# Power_Supply_Section.net
KiCad netlist of a schematic drawn in Altium Designer
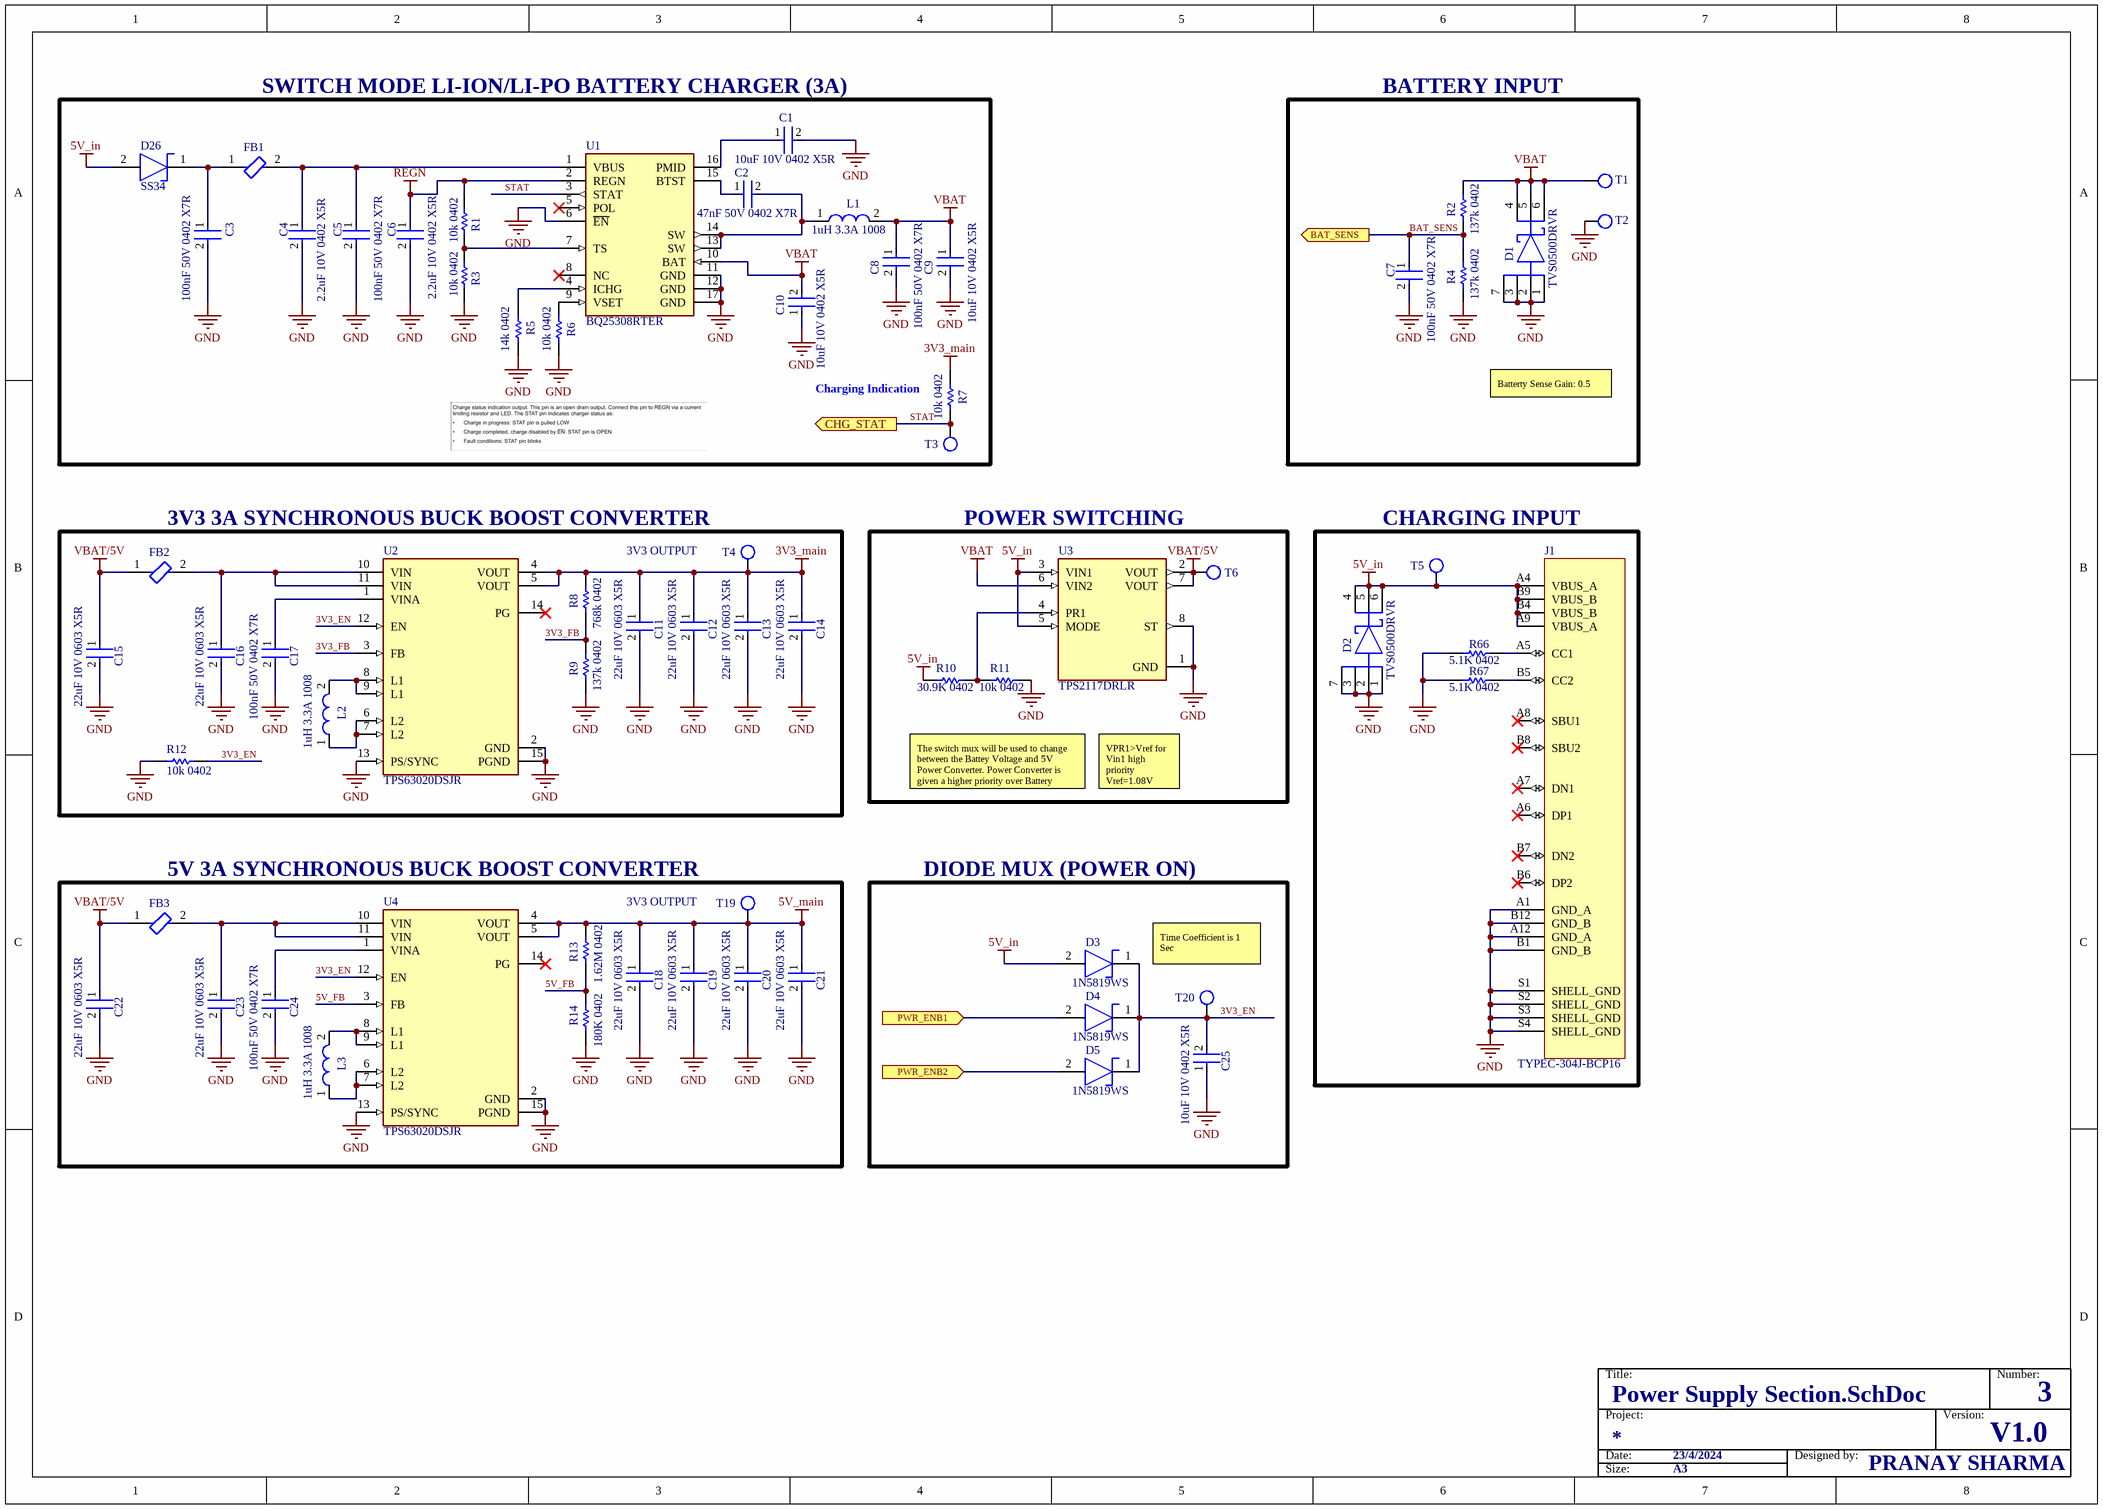
[diagram p0: Power Supply Section.SchDoc]

(export (version "E")
  (design (tool "Eeschema 10.0.6"))
  (components
    (comp (ref "C1")
      (value "10uF 10V 0402 X5R")
      (footprint "Res, Cap, Ind, LED, FB_Lib:0402 IPC CLASS C CAPACITOR")
      (libsource (lib "Capacitor_Lib") (part "10uF 10V 0402 X5R"))
    )
    (comp (ref "C2")
      (value "47nF 50V 0402 X7R")
      (footprint "Res, Cap, Ind, LED, FB_Lib:0402 IPC CLASS C CAPACITOR")
      (libsource (lib "Capacitor_Lib") (part "47nF 50V 0402 X7R"))
    )
    (comp (ref "C3")
      (value "100nF 50V 0402 X7R")
      (footprint "Res, Cap, Ind, LED, FB_Lib:0402 IPC CLASS C CAPACITOR")
      (libsource (lib "Capacitor_Lib") (part "100nF 50V 0402 X7R"))
    )
    (comp (ref "C4")
      (value "2.2uF 10V 0402 X5R")
      (footprint "Res, Cap, Ind, LED, FB_Lib:0402 IPC CLASS C CAPACITOR")
      (libsource (lib "Capacitor_Lib") (part "2.2uF 10V 0402 X5R"))
    )
    (comp (ref "C5")
      (value "100nF 50V 0402 X7R")
      (footprint "Res, Cap, Ind, LED, FB_Lib:0402 IPC CLASS C CAPACITOR")
      (libsource (lib "Capacitor_Lib") (part "100nF 50V 0402 X7R"))
    )
    (comp (ref "C6")
      (value "2.2uF 10V 0402 X5R")
      (footprint "Res, Cap, Ind, LED, FB_Lib:0402 IPC CLASS C CAPACITOR")
      (libsource (lib "Capacitor_Lib") (part "2.2uF 10V 0402 X5R"))
    )
    (comp (ref "C7")
      (value "100nF 50V 0402 X7R")
      (footprint "Res, Cap, Ind, LED, FB_Lib:0402 IPC CLASS C CAPACITOR")
      (libsource (lib "Capacitor_Lib") (part "100nF 50V 0402 X7R"))
    )
    (comp (ref "C8")
      (value "100nF 50V 0402 X7R")
      (footprint "Res, Cap, Ind, LED, FB_Lib:0402 IPC CLASS C CAPACITOR")
      (libsource (lib "Capacitor_Lib") (part "100nF 50V 0402 X7R"))
    )
    (comp (ref "C9")
      (value "10uF 10V 0402 X5R")
      (footprint "Res, Cap, Ind, LED, FB_Lib:0402 IPC CLASS C CAPACITOR")
      (libsource (lib "Capacitor_Lib") (part "10uF 10V 0402 X5R"))
    )
    (comp (ref "C10")
      (value "10uF 10V 0402 X5R")
      (footprint "Res, Cap, Ind, LED, FB_Lib:0402 IPC CLASS C CAPACITOR")
      (libsource (lib "Capacitor_Lib") (part "10uF 10V 0402 X5R"))
    )
    (comp (ref "C11")
      (value "22uF 10V 0603 X5R")
      (footprint "Res, Cap, Ind, LED, FB_Lib:0603 IPC CLASS C CAPACITOR")
      (libsource (lib "Capacitor_Lib") (part "22uF 10V 0603 X5R"))
    )
    (comp (ref "C12")
      (value "22uF 10V 0603 X5R")
      (footprint "Res, Cap, Ind, LED, FB_Lib:0603 IPC CLASS C CAPACITOR")
      (libsource (lib "Capacitor_Lib") (part "22uF 10V 0603 X5R"))
    )
    (comp (ref "C13")
      (value "22uF 10V 0603 X5R")
      (footprint "Res, Cap, Ind, LED, FB_Lib:0603 IPC CLASS C CAPACITOR")
      (libsource (lib "Capacitor_Lib") (part "22uF 10V 0603 X5R"))
    )
    (comp (ref "C14")
      (value "22uF 10V 0603 X5R")
      (footprint "Res, Cap, Ind, LED, FB_Lib:0603 IPC CLASS C CAPACITOR")
      (libsource (lib "Capacitor_Lib") (part "22uF 10V 0603 X5R"))
    )
    (comp (ref "C15")
      (value "22uF 10V 0603 X5R")
      (footprint "Res, Cap, Ind, LED, FB_Lib:0603 IPC CLASS C CAPACITOR")
      (libsource (lib "Capacitor_Lib") (part "22uF 10V 0603 X5R"))
    )
    (comp (ref "C16")
      (value "22uF 10V 0603 X5R")
      (footprint "Res, Cap, Ind, LED, FB_Lib:0603 IPC CLASS C CAPACITOR")
      (libsource (lib "Capacitor_Lib") (part "22uF 10V 0603 X5R"))
    )
    (comp (ref "C17")
      (value "100nF 50V 0402 X7R")
      (footprint "Res, Cap, Ind, LED, FB_Lib:0402 IPC CLASS C CAPACITOR")
      (libsource (lib "Capacitor_Lib") (part "100nF 50V 0402 X7R"))
    )
    (comp (ref "C18")
      (value "22uF 10V 0603 X5R")
      (footprint "Res, Cap, Ind, LED, FB_Lib:0603 IPC CLASS C CAPACITOR")
      (libsource (lib "Capacitor_Lib") (part "22uF 10V 0603 X5R"))
    )
    (comp (ref "C19")
      (value "22uF 10V 0603 X5R")
      (footprint "Res, Cap, Ind, LED, FB_Lib:0603 IPC CLASS C CAPACITOR")
      (libsource (lib "Capacitor_Lib") (part "22uF 10V 0603 X5R"))
    )
    (comp (ref "C20")
      (value "22uF 10V 0603 X5R")
      (footprint "Res, Cap, Ind, LED, FB_Lib:0603 IPC CLASS C CAPACITOR")
      (libsource (lib "Capacitor_Lib") (part "22uF 10V 0603 X5R"))
    )
    (comp (ref "C21")
      (value "22uF 10V 0603 X5R")
      (footprint "Res, Cap, Ind, LED, FB_Lib:0603 IPC CLASS C CAPACITOR")
      (libsource (lib "Capacitor_Lib") (part "22uF 10V 0603 X5R"))
    )
    (comp (ref "C22")
      (value "22uF 10V 0603 X5R")
      (footprint "Res, Cap, Ind, LED, FB_Lib:0603 IPC CLASS C CAPACITOR")
      (libsource (lib "Capacitor_Lib") (part "22uF 10V 0603 X5R"))
    )
    (comp (ref "C23")
      (value "22uF 10V 0603 X5R")
      (footprint "Res, Cap, Ind, LED, FB_Lib:0603 IPC CLASS C CAPACITOR")
      (libsource (lib "Capacitor_Lib") (part "22uF 10V 0603 X5R"))
    )
    (comp (ref "C24")
      (value "100nF 50V 0402 X7R")
      (footprint "Res, Cap, Ind, LED, FB_Lib:0402 IPC CLASS C CAPACITOR")
      (libsource (lib "Capacitor_Lib") (part "100nF 50V 0402 X7R"))
    )
    (comp (ref "C25")
      (value "10uF 10V 0402 X5R")
      (footprint "Res, Cap, Ind, LED, FB_Lib:0402 IPC CLASS C CAPACITOR")
      (libsource (lib "Capacitor_Lib") (part "10uF 10V 0402 X5R"))
    )
    (comp (ref "D1")
      (value "TVS0500DRVR")
      (footprint "Res, Cap, Ind, LED, FB_Lib:DRV0006A IPC-C")
      (libsource (lib "Diodes_Lib") (part "TVS0500DRVR"))
    )
    (comp (ref "D2")
      (value "TVS0500DRVR")
      (footprint "Res, Cap, Ind, LED, FB_Lib:DRV0006A IPC-C")
      (libsource (lib "Diodes_Lib") (part "TVS0500DRVR"))
    )
    (comp (ref "D3")
      (value "1N5819WS")
      (footprint "Res, Cap, Ind, LED, FB_Lib:SOD-323 IPC-C")
      (libsource (lib "Diodes_Lib") (part "1N5819WS"))
    )
    (comp (ref "D4")
      (value "1N5819WS")
      (footprint "Res, Cap, Ind, LED, FB_Lib:SOD-323 IPC-C")
      (libsource (lib "Diodes_Lib") (part "1N5819WS"))
    )
    (comp (ref "D5")
      (value "1N5819WS")
      (footprint "Res, Cap, Ind, LED, FB_Lib:SOD-323 IPC-C")
      (libsource (lib "Diodes_Lib") (part "1N5819WS"))
    )
    (comp (ref "D26")
      (value "SS34")
      (footprint "Res, Cap, Ind, LED, FB_Lib:SS3X Diode IPC-C")
      (libsource (lib "Diodes_Lib") (part "SS34"))
    )
    (comp (ref "FB1")
      (value "BLM21SP111SN1D")
      (footprint "Res, Cap, Ind, LED, FB_Lib:0603 IPC CLASS C FERRITE BEAD")
      (libsource (lib "Ferrite_Bead_Lib") (part "BLM21SP111SN1D"))
    )
    (comp (ref "FB2")
      (value "BLM21SP111SN1D")
      (footprint "Res, Cap, Ind, LED, FB_Lib:0603 IPC CLASS C FERRITE BEAD")
      (libsource (lib "Ferrite_Bead_Lib") (part "BLM21SP111SN1D"))
    )
    (comp (ref "FB3")
      (value "BLM21SP111SN1D")
      (footprint "Res, Cap, Ind, LED, FB_Lib:0603 IPC CLASS C FERRITE BEAD")
      (libsource (lib "Ferrite_Bead_Lib") (part "BLM21SP111SN1D"))
    )
    (comp (ref "J1")
      (value "TYPEC-304J-BCP16")
      (footprint "VALCON_CSP-USC16-TR")
      (libsource (lib "V1.0") (part "USB Type C"))
    )
    (comp (ref "L1")
      (value "1uH 3.3A 1008")
      (footprint "Res, Cap, Ind, LED, FB_Lib:1008 Inductor IPC-C")
      (libsource (lib "Inductor_Lib") (part "DFE252012F-1R0M=P2"))
    )
    (comp (ref "L2")
      (value "1uH 3.3A 1008")
      (footprint "Res, Cap, Ind, LED, FB_Lib:1008 Inductor IPC-C")
      (libsource (lib "Inductor_Lib") (part "DFE252012F-1R0M=P2"))
    )
    (comp (ref "L3")
      (value "1uH 3.3A 1008")
      (footprint "Res, Cap, Ind, LED, FB_Lib:1008 Inductor IPC-C")
      (libsource (lib "Inductor_Lib") (part "DFE252012F-1R0M=P2"))
    )
    (comp (ref "R1")
      (value "10k 0402")
      (footprint "Res, Cap, Ind, LED, FB_Lib:0402 IPC CLASS C RESISTOR")
      (libsource (lib "Resistor_Lib") (part "10k 1% 0402"))
    )
    (comp (ref "R2")
      (value "137k 0402")
      (footprint "Res, Cap, Ind, LED, FB_Lib:0402 IPC CLASS C RESISTOR")
      (libsource (lib "Resistor_Lib") (part "10k 1% 0402"))
    )
    (comp (ref "R3")
      (value "10k 0402")
      (footprint "Res, Cap, Ind, LED, FB_Lib:0402 IPC CLASS C RESISTOR")
      (libsource (lib "Resistor_Lib") (part "10k 1% 0402"))
    )
    (comp (ref "R4")
      (value "137k 0402")
      (footprint "Res, Cap, Ind, LED, FB_Lib:0402 IPC CLASS C RESISTOR")
      (libsource (lib "Resistor_Lib") (part "10k 1% 0402"))
    )
    (comp (ref "R5")
      (value "14k 0402")
      (footprint "Res, Cap, Ind, LED, FB_Lib:0402 IPC CLASS C RESISTOR")
      (libsource (lib "Resistor_Lib") (part "14k 1% 0402"))
    )
    (comp (ref "R6")
      (value "10k 0402")
      (footprint "Res, Cap, Ind, LED, FB_Lib:0402 IPC CLASS C RESISTOR")
      (libsource (lib "Resistor_Lib") (part "10k 1% 0402"))
    )
    (comp (ref "R7")
      (value "10k 0402")
      (footprint "Res, Cap, Ind, LED, FB_Lib:0402 IPC CLASS C RESISTOR")
      (libsource (lib "Resistor_Lib") (part "10k 1% 0402"))
    )
    (comp (ref "R8")
      (value "768k 0402")
      (footprint "Res, Cap, Ind, LED, FB_Lib:0402 IPC CLASS C RESISTOR")
      (libsource (lib "Resistor_Lib") (part "10k 1% 0402"))
    )
    (comp (ref "R9")
      (value "137k 0402")
      (footprint "Res, Cap, Ind, LED, FB_Lib:0402 IPC CLASS C RESISTOR")
      (libsource (lib "Resistor_Lib") (part "10k 1% 0402"))
    )
    (comp (ref "R10")
      (value "30.9K 0402")
      (footprint "Res, Cap, Ind, LED, FB_Lib:0402 IPC CLASS C RESISTOR")
      (libsource (lib "Resistor_Lib") (part "30.9K 1%  0402"))
    )
    (comp (ref "R11")
      (value "10k 0402")
      (footprint "Res, Cap, Ind, LED, FB_Lib:0402 IPC CLASS C RESISTOR")
      (libsource (lib "Resistor_Lib") (part "10k 1% 0402"))
    )
    (comp (ref "R12")
      (value "10k 0402")
      (footprint "Res, Cap, Ind, LED, FB_Lib:0402 IPC CLASS C RESISTOR")
      (libsource (lib "Resistor_Lib") (part "10k 1% 0402"))
    )
    (comp (ref "R13")
      (value "1.62M 0402")
      (footprint "Res, Cap, Ind, LED, FB_Lib:0402 IPC CLASS C RESISTOR")
      (libsource (lib "Resistor_Lib") (part "1.62M 1% 0402"))
    )
    (comp (ref "R14")
      (value "180K 0402")
      (footprint "Res, Cap, Ind, LED, FB_Lib:0402 IPC CLASS C RESISTOR")
      (libsource (lib "Resistor_Lib") (part "180K 1% 0402"))
    )
    (comp (ref "R66")
      (value "5.1K 0402")
      (footprint "Res, Cap, Ind, LED, FB_Lib:0402 IPC CLASS C RESISTOR")
      (libsource (lib "Resistor_Lib") (part "5.1K 1% 0402"))
    )
    (comp (ref "R67")
      (value "5.1K 0402")
      (footprint "Res, Cap, Ind, LED, FB_Lib:0402 IPC CLASS C RESISTOR")
      (libsource (lib "Resistor_Lib") (part "5.1K 1% 0402"))
    )
    (comp (ref "T1")
      (value "Test Point TH")
      (footprint "Miscellaneous_Lib:Test Point TH")
      (libsource (lib "Miscellaneous_Lib") (part "Test Point TH"))
    )
    (comp (ref "T2")
      (value "Test Point TH")
      (footprint "Miscellaneous_Lib:Test Point TH")
      (libsource (lib "Miscellaneous_Lib") (part "Test Point TH"))
    )
    (comp (ref "T3")
      (value "TP")
      (footprint "Miscellaneous_Lib:Testpoint1")
      (libsource (lib "Miscellaneous_Lib") (part "Testpoint1"))
    )
    (comp (ref "T4")
      (value "TP")
      (footprint "Miscellaneous_Lib:Testpoint1")
      (libsource (lib "Miscellaneous_Lib") (part "Testpoint1"))
    )
    (comp (ref "T5")
      (value "TP")
      (footprint "Miscellaneous_Lib:Testpoint1")
      (libsource (lib "Miscellaneous_Lib") (part "Testpoint1"))
    )
    (comp (ref "T6")
      (value "TP")
      (footprint "Miscellaneous_Lib:Testpoint1")
      (libsource (lib "Miscellaneous_Lib") (part "Testpoint1"))
    )
    (comp (ref "T19")
      (value "TP")
      (footprint "Miscellaneous_Lib:Testpoint1")
      (libsource (lib "Miscellaneous_Lib") (part "Testpoint1"))
    )
    (comp (ref "T20")
      (value "TP")
      (footprint "Miscellaneous_Lib:Testpoint1")
      (libsource (lib "Miscellaneous_Lib") (part "Testpoint1"))
    )
    (comp (ref "U1")
      (value "BQ25308RTER")
      (footprint "Integrated_Circuits_Lib:RTE0016C IPC-C")
      (libsource (lib "Integrated_Circuits_Lib") (part "BQ25308RTER"))
    )
    (comp (ref "U2")
      (value "TPS63020DSJR")
      (footprint "FP-DSJ0014A-MFG")
      (libsource (lib "Altium Content Vault") (part "ca84f4b88d1e031d86a58c77b9c066d"))
    )
    (comp (ref "U3")
      (value "TPS2117DRLR")
      (footprint "Integrated_Circuits_Lib:DRL0008A IPC-C")
      (libsource (lib "Integrated_Circuits_Lib") (part "TPS2117DRLR"))
    )
    (comp (ref "U4")
      (value "TPS63020DSJR")
      (footprint "FP-DSJ0014A-MFG")
      (libsource (lib "Altium Content Vault") (part "ca84f4b88d1e031d86a58c77b9c066d"))
    )
  )
  (nets
    (net (code "1") (name "/3V3_EN") (class "Default")
      (node (ref "C25") (pin "2") (pinfunction "2_2") (pintype "passive"))
      (node (ref "D3") (pin "1") (pinfunction "C_1") (pintype "passive"))
      (node (ref "D4") (pin "1") (pinfunction "C_1") (pintype "passive"))
      (node (ref "D5") (pin "1") (pinfunction "C_1") (pintype "passive"))
      (node (ref "R12") (pin "1") (pinfunction "1_1") (pintype "passive"))
      (node (ref "T20") (pin "0") (pinfunction "0_0") (pintype "passive"))
      (node (ref "U2") (pin "12") (pinfunction "EN_12") (pintype "input"))
      (node (ref "U4") (pin "12") (pinfunction "EN_12") (pintype "input"))
    )
    (net (code "2") (name "/3V3_FB") (class "Default")
      (node (ref "R8") (pin "2") (pinfunction "2_2") (pintype "passive"))
      (node (ref "R9") (pin "2") (pinfunction "2_2") (pintype "passive"))
      (node (ref "U2") (pin "3") (pinfunction "FB_3") (pintype "input"))
    )
    (net (code "3") (name "/5V_FB") (class "Default")
      (node (ref "R13") (pin "1") (pinfunction "1_1") (pintype "passive"))
      (node (ref "R14") (pin "2") (pinfunction "2_2") (pintype "passive"))
      (node (ref "U4") (pin "3") (pinfunction "FB_3") (pintype "input"))
    )
    (net (code "4") (name "/BAT_SENS") (class "Default")
      (node (ref "C7") (pin "1") (pinfunction "1_1") (pintype "passive"))
      (node (ref "R2") (pin "1") (pinfunction "1_1") (pintype "passive"))
      (node (ref "R4") (pin "2") (pinfunction "2_2") (pintype "passive"))
    )
    (net (code "5") (name "/PWR_ENB1") (class "Default")
      (node (ref "D4") (pin "2") (pinfunction "A_2") (pintype "passive"))
    )
    (net (code "6") (name "/PWR_ENB2") (class "Default")
      (node (ref "D5") (pin "2") (pinfunction "A_2") (pintype "passive"))
    )
    (net (code "7") (name "/STAT") (class "Default")
      (node (ref "R7") (pin "1") (pinfunction "1_1") (pintype "passive"))
      (node (ref "T3") (pin "0") (pinfunction "0_0") (pintype "passive"))
      (node (ref "U1") (pin "3") (pinfunction "STAT_3") (pintype "output"))
    )
    (net (code "8") (name "3V3_main") (class "Default")
      (node (ref "C11") (pin "1") (pinfunction "1_1") (pintype "passive"))
      (node (ref "C12") (pin "1") (pinfunction "1_1") (pintype "passive"))
      (node (ref "C13") (pin "1") (pinfunction "1_1") (pintype "passive"))
      (node (ref "C14") (pin "1") (pinfunction "1_1") (pintype "passive"))
      (node (ref "R7") (pin "2") (pinfunction "2_2") (pintype "passive"))
      (node (ref "R8") (pin "1") (pinfunction "1_1") (pintype "passive"))
      (node (ref "T4") (pin "0") (pinfunction "0_0") (pintype "passive"))
      (node (ref "U2") (pin "4") (pinfunction "VOUT_4") (pintype "power_in"))
      (node (ref "U2") (pin "5") (pinfunction "VOUT_5") (pintype "power_in"))
    )
    (net (code "9") (name "5V_in") (class "Default")
      (node (ref "D2") (pin "4") (pinfunction "4_4") (pintype "passive"))
      (node (ref "D2") (pin "5") (pinfunction "5_5") (pintype "passive"))
      (node (ref "D2") (pin "6") (pinfunction "6_6") (pintype "passive"))
      (node (ref "D26") (pin "2") (pinfunction "A_2") (pintype "passive"))
      (node (ref "D3") (pin "2") (pinfunction "A_2") (pintype "passive"))
      (node (ref "J1") (pin "A4") (pinfunction "VBUS_A_A4") (pintype "power_in"))
      (node (ref "J1") (pin "A9") (pinfunction "VBUS_A_A9") (pintype "power_in"))
      (node (ref "J1") (pin "B4") (pinfunction "VBUS_B_B4") (pintype "power_in"))
      (node (ref "J1") (pin "B9") (pinfunction "VBUS_B_B9") (pintype "power_in"))
      (node (ref "R10") (pin "2") (pinfunction "2_2") (pintype "passive"))
      (node (ref "T5") (pin "0") (pinfunction "0_0") (pintype "passive"))
      (node (ref "U3") (pin "3") (pinfunction "VIN1_3") (pintype "input"))
      (node (ref "U3") (pin "5") (pinfunction "MODE_5") (pintype "input"))
    )
    (net (code "10") (name "5V_main") (class "Default")
      (node (ref "C18") (pin "1") (pinfunction "1_1") (pintype "passive"))
      (node (ref "C19") (pin "1") (pinfunction "1_1") (pintype "passive"))
      (node (ref "C20") (pin "1") (pinfunction "1_1") (pintype "passive"))
      (node (ref "C21") (pin "1") (pinfunction "1_1") (pintype "passive"))
      (node (ref "R13") (pin "2") (pinfunction "2_2") (pintype "passive"))
      (node (ref "T19") (pin "0") (pinfunction "0_0") (pintype "passive"))
      (node (ref "U4") (pin "4") (pinfunction "VOUT_4") (pintype "power_in"))
      (node (ref "U4") (pin "5") (pinfunction "VOUT_5") (pintype "power_in"))
    )
    (net (code "11") (name "GND") (class "Default")
      (node (ref "C1") (pin "2") (pinfunction "2_2") (pintype "passive"))
      (node (ref "C10") (pin "1") (pinfunction "1_1") (pintype "passive"))
      (node (ref "C11") (pin "2") (pinfunction "2_2") (pintype "passive"))
      (node (ref "C12") (pin "2") (pinfunction "2_2") (pintype "passive"))
      (node (ref "C13") (pin "2") (pinfunction "2_2") (pintype "passive"))
      (node (ref "C14") (pin "2") (pinfunction "2_2") (pintype "passive"))
      (node (ref "C15") (pin "2") (pinfunction "2_2") (pintype "passive"))
      (node (ref "C16") (pin "2") (pinfunction "2_2") (pintype "passive"))
      (node (ref "C17") (pin "2") (pinfunction "2_2") (pintype "passive"))
      (node (ref "C18") (pin "2") (pinfunction "2_2") (pintype "passive"))
      (node (ref "C19") (pin "2") (pinfunction "2_2") (pintype "passive"))
      (node (ref "C20") (pin "2") (pinfunction "2_2") (pintype "passive"))
      (node (ref "C21") (pin "2") (pinfunction "2_2") (pintype "passive"))
      (node (ref "C22") (pin "2") (pinfunction "2_2") (pintype "passive"))
      (node (ref "C23") (pin "2") (pinfunction "2_2") (pintype "passive"))
      (node (ref "C24") (pin "2") (pinfunction "2_2") (pintype "passive"))
      (node (ref "C25") (pin "1") (pinfunction "1_1") (pintype "passive"))
      (node (ref "C3") (pin "2") (pinfunction "2_2") (pintype "passive"))
      (node (ref "C4") (pin "2") (pinfunction "2_2") (pintype "passive"))
      (node (ref "C5") (pin "2") (pinfunction "2_2") (pintype "passive"))
      (node (ref "C6") (pin "2") (pinfunction "2_2") (pintype "passive"))
      (node (ref "C7") (pin "2") (pinfunction "2_2") (pintype "passive"))
      (node (ref "C8") (pin "2") (pinfunction "2_2") (pintype "passive"))
      (node (ref "C9") (pin "2") (pinfunction "2_2") (pintype "passive"))
      (node (ref "D1") (pin "1") (pinfunction "C_1") (pintype "passive"))
      (node (ref "D1") (pin "2") (pinfunction "A_2") (pintype "passive"))
      (node (ref "D1") (pin "3") (pinfunction "3_3") (pintype "passive"))
      (node (ref "D1") (pin "7") (pinfunction "7_7") (pintype "passive"))
      (node (ref "D2") (pin "1") (pinfunction "C_1") (pintype "passive"))
      (node (ref "D2") (pin "2") (pinfunction "A_2") (pintype "passive"))
      (node (ref "D2") (pin "3") (pinfunction "3_3") (pintype "passive"))
      (node (ref "D2") (pin "7") (pinfunction "7_7") (pintype "passive"))
      (node (ref "J1") (pin "A1") (pinfunction "GND_A_A1") (pintype "power_in"))
      (node (ref "J1") (pin "A12") (pinfunction "GND_A_A12") (pintype "power_in"))
      (node (ref "J1") (pin "B1") (pinfunction "GND_B_B1") (pintype "power_in"))
      (node (ref "J1") (pin "B12") (pinfunction "GND_B_B12") (pintype "power_in"))
      (node (ref "J1") (pin "S1") (pinfunction "SHELL_GND_S1") (pintype "power_in"))
      (node (ref "J1") (pin "S2") (pinfunction "SHELL_GND_S2") (pintype "power_in"))
      (node (ref "J1") (pin "S3") (pinfunction "SHELL_GND_S3") (pintype "power_in"))
      (node (ref "J1") (pin "S4") (pinfunction "SHELL_GND_S4") (pintype "power_in"))
      (node (ref "R11") (pin "1") (pinfunction "1_1") (pintype "passive"))
      (node (ref "R12") (pin "2") (pinfunction "2_2") (pintype "passive"))
      (node (ref "R14") (pin "1") (pinfunction "1_1") (pintype "passive"))
      (node (ref "R3") (pin "1") (pinfunction "1_1") (pintype "passive"))
      (node (ref "R4") (pin "1") (pinfunction "1_1") (pintype "passive"))
      (node (ref "R5") (pin "1") (pinfunction "1_1") (pintype "passive"))
      (node (ref "R6") (pin "1") (pinfunction "1_1") (pintype "passive"))
      (node (ref "R66") (pin "1") (pinfunction "1_1") (pintype "passive"))
      (node (ref "R67") (pin "1") (pinfunction "1_1") (pintype "passive"))
      (node (ref "R9") (pin "1") (pinfunction "1_1") (pintype "passive"))
      (node (ref "T2") (pin "0") (pinfunction "0_0") (pintype "passive"))
      (node (ref "U1") (pin "11") (pinfunction "GND_11") (pintype "power_in"))
      (node (ref "U1") (pin "12") (pinfunction "GND_12") (pintype "power_in"))
      (node (ref "U1") (pin "17") (pinfunction "GND_17") (pintype "power_in"))
      (node (ref "U1") (pin "6") (pinfunction "~{EN}_6") (pintype "passive"))
      (node (ref "U2") (pin "13") (pinfunction "PS/SYNC_13") (pintype "input"))
      (node (ref "U2") (pin "15") (pinfunction "PGND_15") (pintype "power_in"))
      (node (ref "U2") (pin "2") (pinfunction "GND_2") (pintype "power_in"))
      (node (ref "U3") (pin "1") (pinfunction "GND_1") (pintype "power_in"))
      (node (ref "U3") (pin "8") (pinfunction "ST_8") (pintype "output"))
      (node (ref "U4") (pin "13") (pinfunction "PS/SYNC_13") (pintype "input"))
      (node (ref "U4") (pin "15") (pinfunction "PGND_15") (pintype "power_in"))
      (node (ref "U4") (pin "2") (pinfunction "GND_2") (pintype "power_in"))
    )
    (net (code "12") (name "Net-(C2-Pad2)") (class "Default")
      (node (ref "C2") (pin "2") (pinfunction "2_2") (pintype "passive"))
      (node (ref "L1") (pin "1") (pinfunction "1_1") (pintype "passive"))
      (node (ref "U1") (pin "13") (pinfunction "SW_13") (pintype "output"))
      (node (ref "U1") (pin "14") (pinfunction "SW_14") (pintype "output"))
    )
    (net (code "13") (name "Net-(C16-Pad1)") (class "Default")
      (node (ref "C16") (pin "1") (pinfunction "1_1") (pintype "passive"))
      (node (ref "FB2") (pin "2") (pinfunction "2_2") (pintype "passive"))
      (node (ref "U2") (pin "10") (pinfunction "VIN_10") (pintype "power_in"))
      (node (ref "U2") (pin "11") (pinfunction "VIN_11") (pintype "power_in"))
    )
    (net (code "14") (name "Net-(C23-Pad1)") (class "Default")
      (node (ref "C23") (pin "1") (pinfunction "1_1") (pintype "passive"))
      (node (ref "FB3") (pin "2") (pinfunction "2_2") (pintype "passive"))
      (node (ref "U4") (pin "10") (pinfunction "VIN_10") (pintype "power_in"))
      (node (ref "U4") (pin "11") (pinfunction "VIN_11") (pintype "power_in"))
    )
    (net (code "15") (name "Net-(D26-C)") (class "Default")
      (node (ref "C3") (pin "1") (pinfunction "1_1") (pintype "passive"))
      (node (ref "D26") (pin "1") (pinfunction "C_1") (pintype "passive"))
      (node (ref "FB1") (pin "1") (pinfunction "1_1") (pintype "passive"))
    )
    (net (code "16") (name "Net-(J1-CC1)") (class "Default")
      (node (ref "J1") (pin "A5") (pinfunction "CC1_A5") (pintype "bidirectional"))
      (node (ref "R66") (pin "2") (pinfunction "2_2") (pintype "passive"))
    )
    (net (code "17") (name "Net-(J1-CC2)") (class "Default")
      (node (ref "J1") (pin "B5") (pinfunction "CC2_B5") (pintype "bidirectional"))
      (node (ref "R67") (pin "2") (pinfunction "2_2") (pintype "passive"))
    )
    (net (code "18") (name "Net-(L2-Pad1)") (class "Default")
      (node (ref "L2") (pin "1") (pinfunction "1_1") (pintype "passive"))
      (node (ref "U2") (pin "6") (pinfunction "L2_6") (pintype "input"))
      (node (ref "U2") (pin "7") (pinfunction "L2_7") (pintype "input"))
    )
    (net (code "19") (name "Net-(L2-Pad2)") (class "Default")
      (node (ref "L2") (pin "2") (pinfunction "2_2") (pintype "passive"))
      (node (ref "U2") (pin "8") (pinfunction "L1_8") (pintype "input"))
      (node (ref "U2") (pin "9") (pinfunction "L1_9") (pintype "input"))
    )
    (net (code "20") (name "Net-(L3-Pad1)") (class "Default")
      (node (ref "L3") (pin "1") (pinfunction "1_1") (pintype "passive"))
      (node (ref "U4") (pin "6") (pinfunction "L2_6") (pintype "input"))
      (node (ref "U4") (pin "7") (pinfunction "L2_7") (pintype "input"))
    )
    (net (code "21") (name "Net-(L3-Pad2)") (class "Default")
      (node (ref "L3") (pin "2") (pinfunction "2_2") (pintype "passive"))
      (node (ref "U4") (pin "8") (pinfunction "L1_8") (pintype "input"))
      (node (ref "U4") (pin "9") (pinfunction "L1_9") (pintype "input"))
    )
    (net (code "22") (name "Net-(U1-BTST)") (class "Default")
      (node (ref "C2") (pin "1") (pinfunction "1_1") (pintype "passive"))
      (node (ref "U1") (pin "15") (pinfunction "BTST_15") (pintype "power_in"))
    )
    (net (code "23") (name "Net-(U1-ICHG)") (class "Default")
      (node (ref "R5") (pin "2") (pinfunction "2_2") (pintype "passive"))
      (node (ref "U1") (pin "4") (pinfunction "ICHG_4") (pintype "input"))
    )
    (net (code "24") (name "Net-(U1-PMID)") (class "Default")
      (node (ref "C1") (pin "1") (pinfunction "1_1") (pintype "passive"))
      (node (ref "U1") (pin "16") (pinfunction "PMID_16") (pintype "power_in"))
    )
    (net (code "25") (name "Net-(U1-TS)") (class "Default")
      (node (ref "R1") (pin "1") (pinfunction "1_1") (pintype "passive"))
      (node (ref "R3") (pin "2") (pinfunction "2_2") (pintype "passive"))
      (node (ref "U1") (pin "7") (pinfunction "TS_7") (pintype "input"))
    )
    (net (code "26") (name "Net-(U1-VBUS)") (class "Default")
      (node (ref "C4") (pin "1") (pinfunction "1_1") (pintype "passive"))
      (node (ref "C5") (pin "1") (pinfunction "1_1") (pintype "passive"))
      (node (ref "FB1") (pin "2") (pinfunction "2_2") (pintype "passive"))
      (node (ref "U1") (pin "1") (pinfunction "VBUS_1") (pintype "power_in"))
    )
    (net (code "27") (name "Net-(U1-VSET)") (class "Default")
      (node (ref "R6") (pin "2") (pinfunction "2_2") (pintype "passive"))
      (node (ref "U1") (pin "9") (pinfunction "VSET_9") (pintype "input"))
    )
    (net (code "28") (name "Net-(U2-VINA)") (class "Default")
      (node (ref "C17") (pin "1") (pinfunction "1_1") (pintype "passive"))
      (node (ref "U2") (pin "1") (pinfunction "VINA_1") (pintype "power_in"))
    )
    (net (code "29") (name "Net-(U3-PR1)") (class "Default")
      (node (ref "R10") (pin "1") (pinfunction "1_1") (pintype "passive"))
      (node (ref "R11") (pin "2") (pinfunction "2_2") (pintype "passive"))
      (node (ref "U3") (pin "4") (pinfunction "PR1_4") (pintype "input"))
    )
    (net (code "30") (name "Net-(U4-VINA)") (class "Default")
      (node (ref "C24") (pin "1") (pinfunction "1_1") (pintype "passive"))
      (node (ref "U4") (pin "1") (pinfunction "VINA_1") (pintype "power_in"))
    )
    (net (code "31") (name "REGN") (class "Default")
      (node (ref "C6") (pin "1") (pinfunction "1_1") (pintype "passive"))
      (node (ref "R1") (pin "2") (pinfunction "2_2") (pintype "passive"))
      (node (ref "U1") (pin "2") (pinfunction "REGN_2") (pintype "power_in"))
    )
    (net (code "32") (name "VBAT") (class "Default")
      (node (ref "C10") (pin "2") (pinfunction "2_2") (pintype "passive"))
      (node (ref "C8") (pin "1") (pinfunction "1_1") (pintype "passive"))
      (node (ref "C9") (pin "1") (pinfunction "1_1") (pintype "passive"))
      (node (ref "D1") (pin "4") (pinfunction "4_4") (pintype "passive"))
      (node (ref "D1") (pin "5") (pinfunction "5_5") (pintype "passive"))
      (node (ref "D1") (pin "6") (pinfunction "6_6") (pintype "passive"))
      (node (ref "L1") (pin "2") (pinfunction "2_2") (pintype "passive"))
      (node (ref "R2") (pin "2") (pinfunction "2_2") (pintype "passive"))
      (node (ref "T1") (pin "0") (pinfunction "0_0") (pintype "passive"))
      (node (ref "U1") (pin "10") (pinfunction "BAT_10") (pintype "input"))
      (node (ref "U3") (pin "6") (pinfunction "VIN2_6") (pintype "input"))
    )
    (net (code "33") (name "VBAT{slash}5V") (class "Default")
      (node (ref "C15") (pin "1") (pinfunction "1_1") (pintype "passive"))
      (node (ref "C22") (pin "1") (pinfunction "1_1") (pintype "passive"))
      (node (ref "FB2") (pin "1") (pinfunction "1_1") (pintype "passive"))
      (node (ref "FB3") (pin "1") (pinfunction "1_1") (pintype "passive"))
      (node (ref "T6") (pin "0") (pinfunction "0_0") (pintype "passive"))
      (node (ref "U3") (pin "2") (pinfunction "VOUT_2") (pintype "output"))
      (node (ref "U3") (pin "7") (pinfunction "VOUT_7") (pintype "output"))
    )
    (net (code "34") (name "unconnected-(J1-DN1-PadA7)") (class "Default")
      (node (ref "J1") (pin "A7") (pinfunction "DN1_A7") (pintype "bidirectional+no_connect"))
    )
    (net (code "35") (name "unconnected-(J1-DN2-PadB7)") (class "Default")
      (node (ref "J1") (pin "B7") (pinfunction "DN2_B7") (pintype "bidirectional+no_connect"))
    )
    (net (code "36") (name "unconnected-(J1-DP1-PadA6)") (class "Default")
      (node (ref "J1") (pin "A6") (pinfunction "DP1_A6") (pintype "bidirectional+no_connect"))
    )
    (net (code "37") (name "unconnected-(J1-DP2-PadB6)") (class "Default")
      (node (ref "J1") (pin "B6") (pinfunction "DP2_B6") (pintype "bidirectional+no_connect"))
    )
    (net (code "38") (name "unconnected-(J1-SBU1-PadA8)") (class "Default")
      (node (ref "J1") (pin "A8") (pinfunction "SBU1_A8") (pintype "bidirectional+no_connect"))
    )
    (net (code "39") (name "unconnected-(J1-SBU2-PadB8)") (class "Default")
      (node (ref "J1") (pin "B8") (pinfunction "SBU2_B8") (pintype "bidirectional+no_connect"))
    )
    (net (code "40") (name "unconnected-(U1-NC-Pad8)") (class "Default")
      (node (ref "U1") (pin "8") (pinfunction "NC_8") (pintype "passive+no_connect"))
    )
    (net (code "41") (name "unconnected-(U1-POL-Pad5)") (class "Default")
      (node (ref "U1") (pin "5") (pinfunction "POL_5") (pintype "input+no_connect"))
    )
    (net (code "42") (name "unconnected-(U2-PG-Pad14)") (class "Default")
      (node (ref "U2") (pin "14") (pinfunction "PG_14") (pintype "open_collector+no_connect"))
    )
    (net (code "43") (name "unconnected-(U4-PG-Pad14)") (class "Default")
      (node (ref "U4") (pin "14") (pinfunction "PG_14") (pintype "open_collector+no_connect"))
    )
  )
)
